# Sheet1.net
KiCad netlist of a schematic drawn in Altium Designer
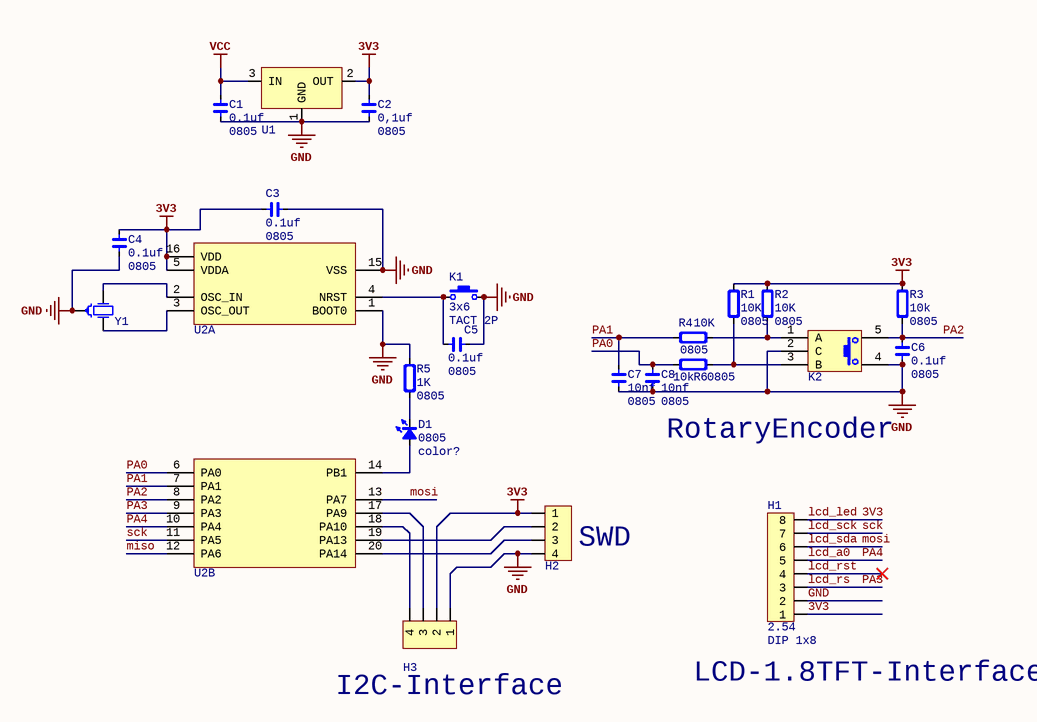
[diagram p0: Sheet1.SchDoc]

(export (version "E")
  (design (tool "Eeschema 10.0.6"))
  (components
    (comp (ref "C1")
      (value "0.1uf")
      (footprint "PCB_PassiveCap:CAP_0805")
      (description "Capacitor")
      (fields (field (name "TYPE") "0805") (field (name "Comment") "HDR2x10_2.54"))
      (libsource (lib "") (part "Cap_0805_2"))
    )
    (comp (ref "C2")
      (value "0,1uf")
      (footprint "PCB_PassiveCap:CAP_0805")
      (description "Capacitor")
      (fields (field (name "TYPE") "0805") (field (name "Comment") "HDR2x10_2.54"))
      (libsource (lib "") (part "Cap_0805_2"))
    )
    (comp (ref "C3")
      (value "0.1uf")
      (footprint "PCB_PassiveCap:CAP_0805")
      (description "Capacitor")
      (fields (field (name "TYPE") "0805") (field (name "Comment") "HDR2x10_2.54"))
      (libsource (lib "") (part "Cap_0805_1"))
    )
    (comp (ref "C4")
      (value "0.1uf")
      (footprint "PCB_PassiveCap:CAP_0805")
      (description "Capacitor")
      (fields (field (name "TYPE") "0805") (field (name "Comment") "HDR2x10_2.54"))
      (libsource (lib "SCH_Passive") (part "Cap_0805"))
    )
    (comp (ref "C5")
      (value "0.1uf")
      (footprint "PCB_PassiveCap:CAP_0805")
      (description "Capacitor")
      (fields (field (name "TYPE") "0805") (field (name "Comment") "HDR2x10_2.54"))
      (libsource (lib "") (part "Cap_0805_1"))
    )
    (comp (ref "C6")
      (value "0.1uf")
      (footprint "PCB_PassiveCap:CAP_0805")
      (description "Capacitor")
      (fields (field (name "TYPE") "0805") (field (name "Comment") "HDR2x10_2.54"))
      (libsource (lib "") (part "Cap_0805_2"))
    )
    (comp (ref "C7")
      (value "10nf")
      (footprint "PCB_PassiveCap:CAP_0805")
      (description "Capacitor")
      (fields (field (name "TYPE") "0805") (field (name "Comment") "HDR2x10_2.54"))
      (libsource (lib "") (part "Cap_0805_2"))
    )
    (comp (ref "C8")
      (value "10nf")
      (footprint "PCB_PassiveCap:CAP_0805")
      (description "Capacitor")
      (fields (field (name "TYPE") "0805") (field (name "Comment") "HDR2x10_2.54"))
      (libsource (lib "") (part "Cap_0805_2"))
    )
    (comp (ref "D1")
      (value "color?")
      (footprint "PCB_ActiveLED:LED_0805_RED")
      (description "LED")
      (fields (field (name "TYPE") "0805") (field (name "Comment") "HDR2x10_2.54"))
      (libsource (lib "SCH_Active") (part "LED_0805"))
    )
    (comp (ref "H1")
      (value "2.54")
      (footprint "PCB_ConnectorHDR:HDR1X8_2.54_180")
      (description "Header")
      (fields (field (name "TYPE") "DIP 1x8") (field (name "Comment") "HDR2x10_2.54"))
      (libsource (lib "SCH_ConnectorHDR") (part "HDR1x8_2.54"))
    )
    (comp (ref "H2")
      (value "HDR2x10_2.54")
      (footprint "PCB_ConnectorHDR:HDR1x4_2.54_180")
      (description "Header")
      (libsource (lib "SCH_ConnectorHDR") (part "HDR1x4_2.54"))
    )
    (comp (ref "H3")
      (value "HDR2x10_2.54")
      (footprint "PCB_ConnectorHDR:HDR1x4_2.54_180")
      (description "Header")
      (libsource (lib "") (part "HDR1x4_2.54_1"))
    )
    (comp (ref "K1")
      (value "3x6")
      (footprint "PCB_Switch:ButtonTACT_3x6x2.5_180")
      (description "Button")
      (fields (field (name "TYPE") "TACT 2P") (field (name "Comment") "HDR2x10_2.54"))
      (libsource (lib "SCH_Switch") (part "ButtonTACT_3x6x2.5_180"))
    )
    (comp (ref "K2")
      (value "HDR2x10_2.54")
      (footprint "PCB_Switch:RotaryEncoder")
      (description "Encoder")
      (libsource (lib "SCH_Switch") (part "RotaryEncoder"))
    )
    (comp (ref "R1")
      (value "10K")
      (footprint "PCB_PassiveRes:RES_0805")
      (description "Resistor")
      (fields (field (name "TYPE") "0805") (field (name "Comment") "HDR2x10_2.54"))
      (libsource (lib "SCH_Passive") (part "Res_0805"))
    )
    (comp (ref "R2")
      (value "10K")
      (footprint "PCB_PassiveRes:RES_0805")
      (description "Resistor")
      (fields (field (name "TYPE") "0805") (field (name "Comment") "HDR2x10_2.54"))
      (libsource (lib "SCH_Passive") (part "Res_0805"))
    )
    (comp (ref "R3")
      (value "10k")
      (footprint "PCB_PassiveRes:RES_0805")
      (description "Resistor")
      (fields (field (name "TYPE") "0805") (field (name "Comment") "HDR2x10_2.54"))
      (libsource (lib "SCH_Passive") (part "Res_0805"))
    )
    (comp (ref "R4")
      (value "10K")
      (footprint "PCB_PassiveRes:RES_0805")
      (description "Resistor")
      (fields (field (name "TYPE") "0805") (field (name "Comment") "HDR2x10_2.54"))
      (libsource (lib "SCH_Passive") (part "Res_0805"))
    )
    (comp (ref "R5")
      (value "1K")
      (footprint "PCB_PassiveRes:RES_0805")
      (description "Resistor")
      (fields (field (name "TYPE") "0805") (field (name "Comment") "HDR2x10_2.54"))
      (libsource (lib "SCH_Passive") (part "Res_0805"))
    )
    (comp (ref "R6")
      (value "10k")
      (footprint "PCB_PassiveRes:RES_0805")
      (description "Resistor")
      (fields (field (name "TYPE") "0805") (field (name "Comment") "HDR2x10_2.54"))
      (libsource (lib "SCH_Passive") (part "Res_0805"))
    )
    (comp (ref "U1")
      (value "HDR2x10_2.54")
      (footprint "PCB_IntegratedCircuit:SOT223-3")
      (description "Power")
      (libsource (lib "SCH_IntegratedCircuit") (part "TLV1117"))
    )
    (comp (ref "U2")
      (value "HDR2x10_2.54")
      (footprint "PCB_IntegratedCircuit:TSSOP_E170_P0.65_20")
      (description "MCU")
      (libsource (lib "SCH_IntegratedCircuit") (part "STM32F03xF"))
    )
    (comp (ref "Y1")
      (value "HDR2x10_2.54")
      (footprint "XTAL_3P_CSTCE_8M_3.2*1.3")
      (description "murata CSTCE 8M 3.2*1.3")
      (libsource (lib "SCH_Oscillator") (part "XTAL-3PIN"))
    )
  )
  (nets
    (net (code "1") (name "/PA0") (class "Default")
      (node (ref "C8") (pin "2") (pinfunction "2_2") (pintype "passive"))
      (node (ref "R6") (pin "1") (pinfunction "1_1") (pintype "passive"))
      (node (ref "U2") (pin "6") (pinfunction "PA0_6") (pintype "passive"))
    )
    (net (code "2") (name "/PA1") (class "Default")
      (node (ref "C7") (pin "2") (pinfunction "2_2") (pintype "passive"))
      (node (ref "R4") (pin "1") (pinfunction "1_1") (pintype "passive"))
      (node (ref "U2") (pin "7") (pinfunction "PA1_7") (pintype "passive"))
    )
    (net (code "3") (name "/PA2") (class "Default")
      (node (ref "C6") (pin "2") (pinfunction "2_2") (pintype "passive"))
      (node (ref "K2") (pin "5") (pinfunction "5_5") (pintype "passive"))
      (node (ref "R3") (pin "2") (pinfunction "2_2") (pintype "passive"))
      (node (ref "U2") (pin "8") (pinfunction "PA2_8") (pintype "passive"))
    )
    (net (code "4") (name "/PA3") (class "Default")
      (node (ref "H1") (pin "3") (pinfunction "3_3") (pintype "passive"))
      (node (ref "U2") (pin "9") (pinfunction "PA3_9") (pintype "passive"))
    )
    (net (code "5") (name "/PA4") (class "Default")
      (node (ref "H1") (pin "5") (pinfunction "5_5") (pintype "passive"))
      (node (ref "U2") (pin "10") (pinfunction "PA4_10") (pintype "passive"))
    )
    (net (code "6") (name "/lcd_rst") (class "Default")
      (node (ref "H1") (pin "4") (pinfunction "4_4") (pintype "passive+no_connect"))
    )
    (net (code "7") (name "/lcd_sck") (class "Default")
      (node (ref "H1") (pin "7") (pinfunction "7_7") (pintype "passive"))
      (node (ref "U2") (pin "11") (pinfunction "PA5_11") (pintype "passive"))
    )
    (net (code "8") (name "/lcd_sda") (class "Default")
      (node (ref "H1") (pin "6") (pinfunction "6_6") (pintype "passive"))
      (node (ref "U2") (pin "13") (pinfunction "PA7_13") (pintype "passive"))
    )
    (net (code "9") (name "/miso") (class "Default")
      (node (ref "U2") (pin "12") (pinfunction "PA6_12") (pintype "passive"))
    )
    (net (code "10") (name "3V3") (class "Default")
      (node (ref "C2") (pin "2") (pinfunction "2_2") (pintype "passive"))
      (node (ref "C3") (pin "2") (pinfunction "2_2") (pintype "passive"))
      (node (ref "C4") (pin "1") (pinfunction "1_1") (pintype "passive"))
      (node (ref "H1") (pin "1") (pinfunction "1_1") (pintype "passive"))
      (node (ref "H1") (pin "8") (pinfunction "8_8") (pintype "passive"))
      (node (ref "H2") (pin "1") (pinfunction "1_1") (pintype "passive"))
      (node (ref "H3") (pin "2") (pinfunction "2_2") (pintype "passive"))
      (node (ref "R1") (pin "2") (pinfunction "2_2") (pintype "passive"))
      (node (ref "R2") (pin "2") (pinfunction "2_2") (pintype "passive"))
      (node (ref "R3") (pin "1") (pinfunction "1_1") (pintype "passive"))
      (node (ref "U1") (pin "2") (pinfunction "OUT_2") (pintype "power_in"))
      (node (ref "U2") (pin "16") (pinfunction "VDD_16") (pintype "passive"))
      (node (ref "U2") (pin "5") (pinfunction "VDDA_5") (pintype "passive"))
    )
    (net (code "11") (name "GND") (class "Default")
      (node (ref "C1") (pin "1") (pinfunction "1_1") (pintype "passive"))
      (node (ref "C2") (pin "1") (pinfunction "1_1") (pintype "passive"))
      (node (ref "C3") (pin "1") (pinfunction "1_1") (pintype "passive"))
      (node (ref "C4") (pin "2") (pinfunction "2_2") (pintype "passive"))
      (node (ref "C5") (pin "1") (pinfunction "1_1") (pintype "passive"))
      (node (ref "C6") (pin "1") (pinfunction "1_1") (pintype "passive"))
      (node (ref "C7") (pin "1") (pinfunction "1_1") (pintype "passive"))
      (node (ref "C8") (pin "1") (pinfunction "1_1") (pintype "passive"))
      (node (ref "H1") (pin "2") (pinfunction "2_2") (pintype "passive"))
      (node (ref "H2") (pin "4") (pinfunction "4_4") (pintype "passive"))
      (node (ref "H3") (pin "1") (pinfunction "1_1") (pintype "passive"))
      (node (ref "K1") (pin "2") (pinfunction "2_2") (pintype "passive"))
      (node (ref "K2") (pin "2") (pinfunction "C_2") (pintype "passive"))
      (node (ref "K2") (pin "4") (pinfunction "4_4") (pintype "passive"))
      (node (ref "R5") (pin "2") (pinfunction "2_2") (pintype "passive"))
      (node (ref "U1") (pin "1") (pinfunction "GND_1") (pintype "power_in"))
      (node (ref "U2") (pin "1") (pinfunction "BOOT0_1") (pintype "passive"))
      (node (ref "U2") (pin "15") (pinfunction "VSS_15") (pintype "passive"))
      (node (ref "Y1") (pin "2") (pinfunction "GND_2") (pintype "passive"))
    )
    (net (code "12") (name "Net-(D1-A)") (class "Default")
      (node (ref "D1") (pin "1") (pinfunction "A_1") (pintype "passive"))
      (node (ref "U2") (pin "14") (pinfunction "PB1_14") (pintype "passive"))
    )
    (net (code "13") (name "Net-(D1-K)") (class "Default")
      (node (ref "D1") (pin "2") (pinfunction "K_2") (pintype "passive"))
      (node (ref "R5") (pin "1") (pinfunction "1_1") (pintype "passive"))
    )
    (net (code "14") (name "Net-(K2-A)") (class "Default")
      (node (ref "K2") (pin "1") (pinfunction "A_1") (pintype "passive"))
      (node (ref "R2") (pin "1") (pinfunction "1_1") (pintype "passive"))
      (node (ref "R4") (pin "2") (pinfunction "2_2") (pintype "passive"))
    )
    (net (code "15") (name "Net-(K2-B)") (class "Default")
      (node (ref "K2") (pin "3") (pinfunction "B_3") (pintype "passive"))
      (node (ref "R1") (pin "1") (pinfunction "1_1") (pintype "passive"))
      (node (ref "R6") (pin "2") (pinfunction "2_2") (pintype "passive"))
    )
    (net (code "16") (name "Net-(U2A-NRST)") (class "Default")
      (node (ref "C5") (pin "2") (pinfunction "2_2") (pintype "passive"))
      (node (ref "K1") (pin "1") (pinfunction "1_1") (pintype "passive"))
      (node (ref "U2") (pin "4") (pinfunction "NRST_4") (pintype "passive"))
    )
    (net (code "17") (name "Net-(U2A-OSC_IN)") (class "Default")
      (node (ref "U2") (pin "2") (pinfunction "OSC_IN_2") (pintype "passive"))
      (node (ref "Y1") (pin "1") (pinfunction "OSC1_1") (pintype "passive"))
    )
    (net (code "18") (name "Net-(U2A-OSC_OUT)") (class "Default")
      (node (ref "U2") (pin "3") (pinfunction "OSC_OUT_3") (pintype "passive"))
      (node (ref "Y1") (pin "3") (pinfunction "OSC2_3") (pintype "passive"))
    )
    (net (code "19") (name "Net-(U2B-PA9)") (class "Default")
      (node (ref "H3") (pin "3") (pinfunction "3_3") (pintype "passive"))
      (node (ref "U2") (pin "17") (pinfunction "PA9_17") (pintype "passive"))
    )
    (net (code "20") (name "Net-(U2B-PA10)") (class "Default")
      (node (ref "H3") (pin "4") (pinfunction "4_4") (pintype "passive"))
      (node (ref "U2") (pin "18") (pinfunction "PA10_18") (pintype "passive"))
    )
    (net (code "21") (name "Net-(U2B-PA13)") (class "Default")
      (node (ref "H2") (pin "2") (pinfunction "2_2") (pintype "passive"))
      (node (ref "U2") (pin "19") (pinfunction "PA13_19") (pintype "passive"))
    )
    (net (code "22") (name "Net-(U2B-PA14)") (class "Default")
      (node (ref "H2") (pin "3") (pinfunction "3_3") (pintype "passive"))
      (node (ref "U2") (pin "20") (pinfunction "PA14_20") (pintype "passive"))
    )
    (net (code "23") (name "VCC") (class "Default")
      (node (ref "C1") (pin "2") (pinfunction "2_2") (pintype "passive"))
      (node (ref "U1") (pin "3") (pinfunction "IN_3") (pintype "power_in"))
    )
  )
)
